# Motor_Controller_V_5.net
KiCad netlist of a schematic drawn in EAGLE
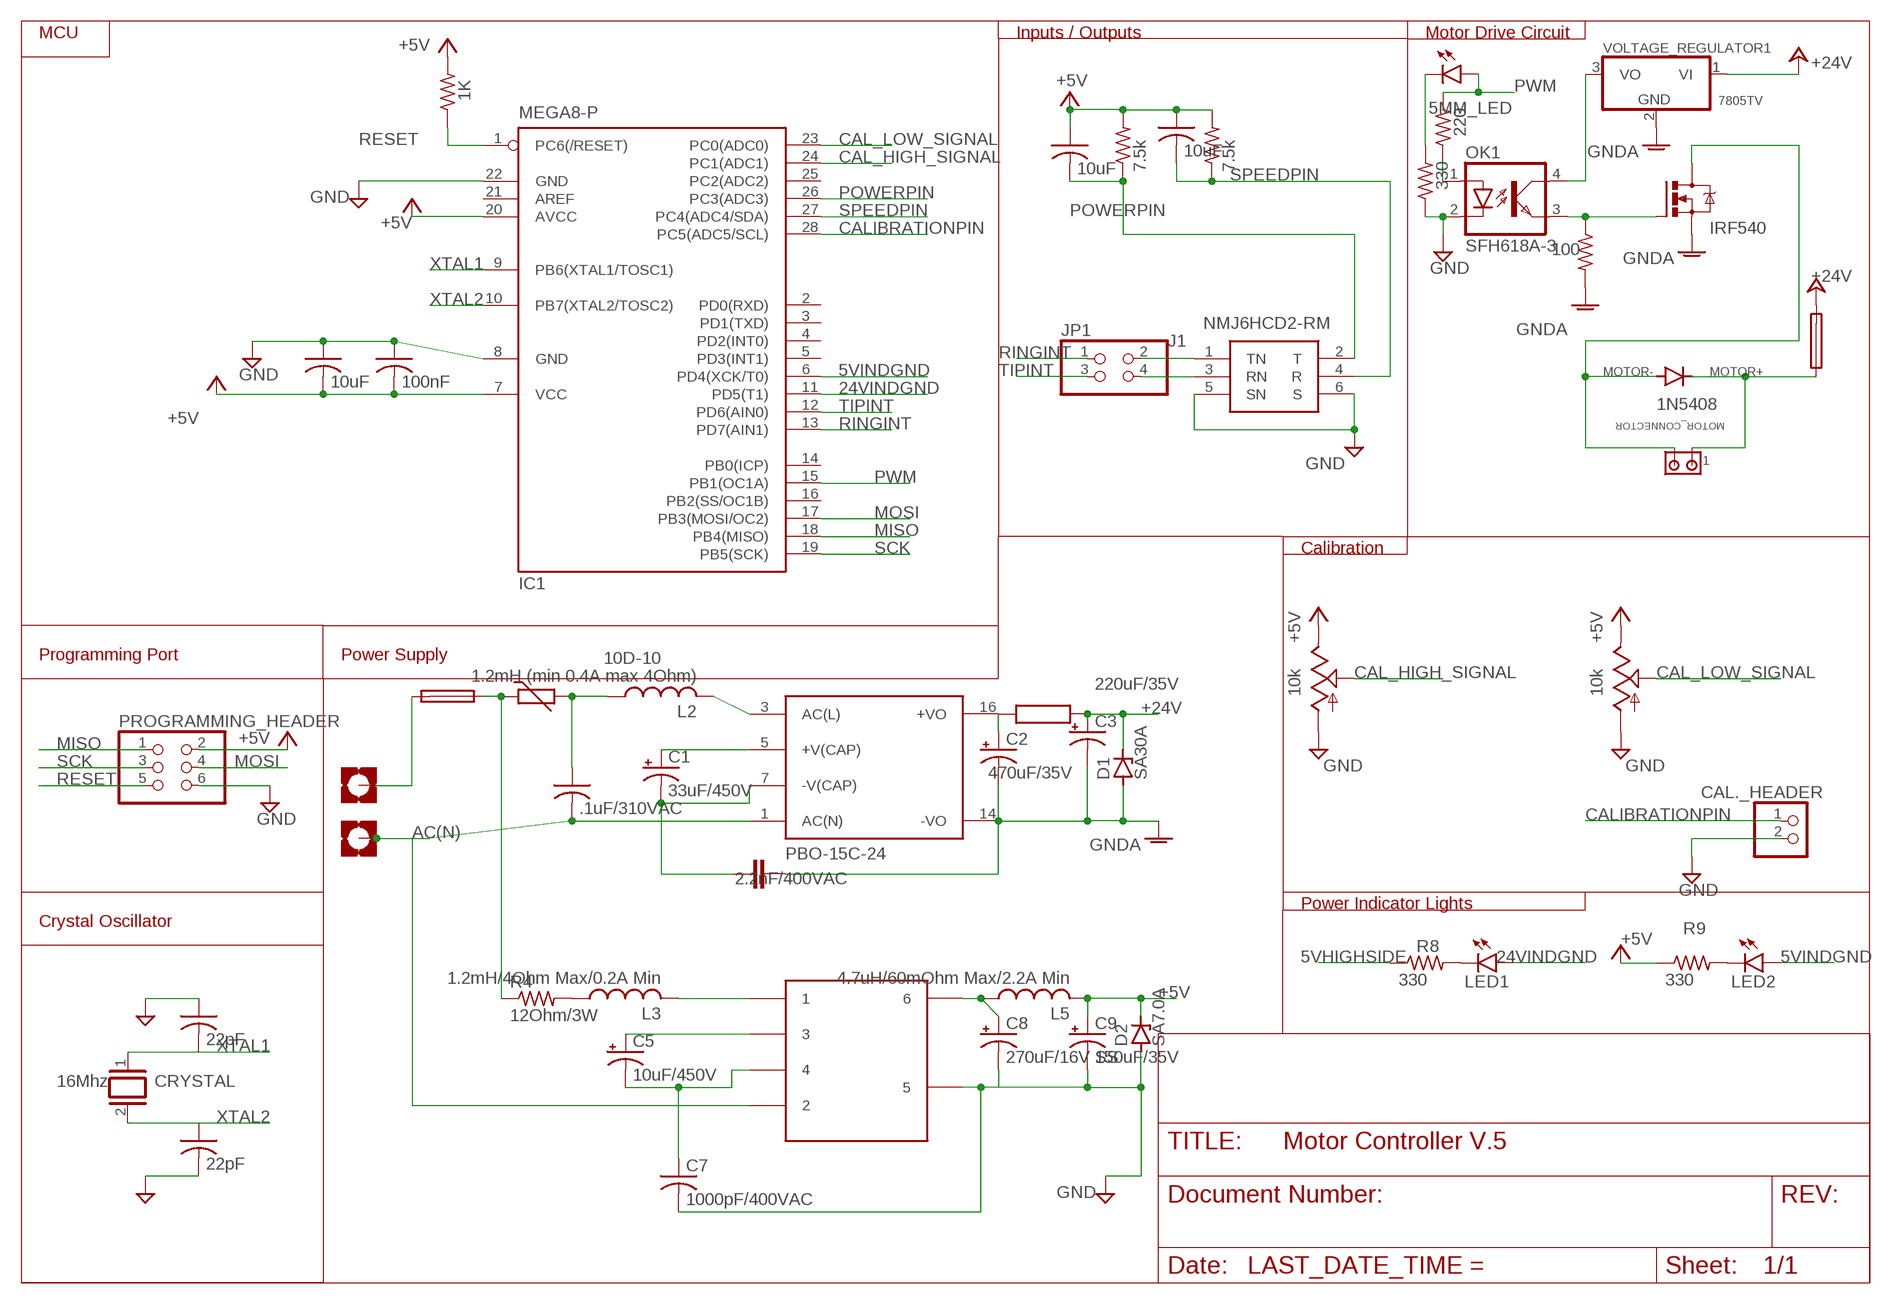
[diagram p0: schematic, sheet 1]

(export (version "E")
  (design (tool "Eeschema 10.0.6"))
  (components
    (comp (ref "1N5408")
      (value "1N5408")
      (footprint "eagle-import:DO201-15")
      (fields (field (name "MF") "VISHAY") (field (name "MPN") "1N5408-E3/54"))
      (libsource (lib "eagle-import") (part "1N5400"))
    )
    (comp (ref "AC(N)")
      (value "PAD3.0")
      (footprint "eagle-import:3,0-PAD-SQUARE")
      (libsource (lib "eagle-import") (part "PAD3.0"))
    )
    (comp (ref "C1")
      (value "33uF/450V")
      (footprint "eagle-import:E5-13")
      (libsource (lib "eagle-import") (part "CPOL-USE5-13"))
    )
    (comp (ref "C2")
      (value "470uF/35V")
      (footprint "eagle-import:E5-10,5")
      (fields (field (name "MF") "PANASONIC") (field (name "MPN") "ECA1VHG471B"))
      (libsource (lib "eagle-import") (part "CPOL-USE5-10.5"))
    )
    (comp (ref "C3")
      (value "220uF/35V")
      (footprint "eagle-import:E5-10,5")
      (fields (field (name "MF") "KEMET") (field (name "MPN") "A768KS227M1VLAE024"))
      (libsource (lib "eagle-import") (part "CPOL-USE5-10.5"))
    )
    (comp (ref "C4")
      (value ".1uF/310VAC")
      (footprint "eagle-import:C102-064X133")
      (libsource (lib "eagle-import") (part "CMPP_AC275V104K10S6"))
    )
    (comp (ref "C5")
      (value "10uF/450V")
      (footprint "eagle-import:E5-10,5")
      (libsource (lib "eagle-import") (part "CPOL-USE5-10.5"))
    )
    (comp (ref "C6")
      (value "22pF")
      (footprint "eagle-import:C025-024X044")
      (libsource (lib "eagle-import") (part "C-US025-024X044"))
    )
    (comp (ref "C7")
      (value "1000pF/400VAC")
      (footprint "eagle-import:C075-052X106")
      (libsource (lib "eagle-import") (part "C-US075-052X106"))
    )
    (comp (ref "C8")
      (value "270uF/16V SS")
      (footprint "eagle-import:E2,5-6")
      (libsource (lib "eagle-import") (part "CPOL-USE2.5-6"))
    )
    (comp (ref "C9")
      (value "150uF/35V")
      (footprint "eagle-import:E3,5-8")
      (libsource (lib "eagle-import") (part "CPOL-USE3.5-8"))
    )
    (comp (ref "C10")
      (value "10uF")
      (footprint "eagle-import:C025-024X044")
      (libsource (lib "eagle-import") (part "C-US025-024X044"))
    )
    (comp (ref "C12")
      (value "10uF")
      (footprint "eagle-import:C025-024X044")
      (libsource (lib "eagle-import") (part "C-US025-024X044"))
    )
    (comp (ref "C13")
      (value "10uF")
      (footprint "eagle-import:C025-024X044")
      (libsource (lib "eagle-import") (part "C-US025-024X044"))
    )
    (comp (ref "C14")
      (value "100nF")
      (footprint "eagle-import:C025-024X044")
      (libsource (lib "eagle-import") (part "C-US025-024X044"))
    )
    (comp (ref "C15")
      (value "22pF")
      (footprint "eagle-import:C025-024X044")
      (libsource (lib "eagle-import") (part "C-US025-024X044"))
    )
    (comp (ref "CAL._HEADER")
      (value "PINHD-1X2")
      (footprint "eagle-import:1X02")
      (libsource (lib "eagle-import") (part "PINHD-1X2"))
    )
    (comp (ref "CRYSTAL")
      (value "16Mhz")
      (footprint "eagle-import:QS")
      (libsource (lib "eagle-import") (part "XTAL/S"))
    )
    (comp (ref "CY1")
      (value "2.2nF/400VAC")
      (footprint "eagle-import:YC10B4")
      (libsource (lib "eagle-import") (part "CYYC10B4"))
    )
    (comp (ref "D1")
      (value "SA30A")
      (footprint "eagle-import:TVS-10")
      (libsource (lib "eagle-import") (part "TVSDIO"))
    )
    (comp (ref "D2")
      (value "SA7.0A")
      (footprint "eagle-import:TVS-10")
      (libsource (lib "eagle-import") (part "TVSDIO"))
    )
    (comp (ref "F1")
      (value "FUSESH22,5")
      (footprint "eagle-import:SH22,5")
      (libsource (lib "eagle-import") (part "FUSESH22,5"))
    )
    (comp (ref "F2")
      (value "1A/300V")
      (footprint "eagle-import:SH22,5")
      (libsource (lib "eagle-import") (part "FUSESH22,5"))
    )
    (comp (ref "FAST")
      (value "10k")
      (footprint "eagle-import:CT6")
      (libsource (lib "eagle-import") (part "TRIM_US-CT6"))
    )
    (comp (ref "H1")
      (value "PAD3.0")
      (footprint "eagle-import:3,0-PAD-SQUARE")
      (libsource (lib "eagle-import") (part "PAD3.0"))
    )
    (comp (ref "IC1")
      (value "MEGA8-P")
      (footprint "eagle-import:DIL28-3")
      (libsource (lib "eagle-import") (part "MEGA8-P"))
    )
    (comp (ref "J1")
      (value "NMJ6HCD2-RM")
      (footprint "eagle-import:NMJ6HCD2RM")
      (fields (field (name "MOUSER_PART_NUMBER") "568-NMJ6HCD2-RM"))
      (libsource (lib "eagle-import") (part "NMJ6HCD2-RM"))
    )
    (comp (ref "JP1")
      (value "PINHD-2X2")
      (footprint "eagle-import:2X02")
      (libsource (lib "eagle-import") (part "PINHD-2X2"))
    )
    (comp (ref "L2")
      (value "1.2mH (min 0.4A max 4Ohm)")
      (footprint "eagle-import:RCP1317_INDUCTOR")
      (libsource (lib "eagle-import") (part "RCP_1317_INDUCTOR"))
    )
    (comp (ref "L3")
      (value "1.2mH/4Ohm Max/0.2A Min")
      (footprint "eagle-import:RCP1317_INDUCTOR")
      (libsource (lib "eagle-import") (part "RCP_1317_INDUCTOR"))
    )
    (comp (ref "L5")
      (value "4.7uH/60mOhm Max/2.2A Min")
      (footprint "eagle-import:RLB0914_INDUCTOR")
      (libsource (lib "eagle-import") (part "RLB0914_INDUCTOR"))
    )
    (comp (ref "LED1")
      (value "LED3MM")
      (footprint "eagle-import:LED3MM")
      (libsource (lib "eagle-import") (part "LED3MM"))
    )
    (comp (ref "LED2")
      (value "LED3MM")
      (footprint "eagle-import:LED3MM")
      (libsource (lib "eagle-import") (part "LED3MM"))
    )
    (comp (ref "MOTOR_CONNECTOR")
      (value "MATE-N-LOK_193839-1")
      (footprint "eagle-import:MATE-N-LOK_2PIN_CONNECTOR")
      (libsource (lib "eagle-import") (part "MATE-N-LOK_193839-1"))
    )
    (comp (ref "OK1")
      (value "SFH618A-3")
      (footprint "eagle-import:DIP4")
      (fields (field (name "MF") "VISHAY/TELEFUNKEN"))
      (libsource (lib "eagle-import") (part "SFH618?A-3"))
    )
    (comp (ref "PROGRAMMING_HEADER")
      (value "PINHD-2X3")
      (footprint "eagle-import:2X03")
      (libsource (lib "eagle-import") (part "PINHD-2X3"))
    )
    (comp (ref "PS1")
      (value "PBO-15C-24")
      (footprint "eagle-import:CONV_PBO-15C-24")
      (fields (field (name "MF") "CUI Inc."))
      (libsource (lib "eagle-import") (part "PBO-15C-24"))
    )
    (comp (ref "Q1")
      (value "IRF540")
      (footprint "eagle-import:TO220BV")
      (libsource (lib "eagle-import") (part "IRF540"))
    )
    (comp (ref "R1")
      (value "10D-10")
      (footprint "eagle-import:R-7,5")
      (libsource (lib "eagle-import") (part "THERMISTOR-7,5"))
    )
    (comp (ref "R2")
      (value "1K")
      (footprint "eagle-import:0204_7")
      (libsource (lib "eagle-import") (part "R-US_0204/7"))
    )
    (comp (ref "R3")
      (value "7.5k")
      (footprint "eagle-import:0204_7")
      (libsource (lib "eagle-import") (part "R-US_0204/7"))
    )
    (comp (ref "R4")
      (value "12Ohm/3W")
      (footprint "eagle-import:VTA52")
      (libsource (lib "eagle-import") (part "R-US_VTA52"))
    )
    (comp (ref "R5")
      (value "220")
      (footprint "eagle-import:0204_7")
      (libsource (lib "eagle-import") (part "R-US_0204/7"))
    )
    (comp (ref "R6")
      (value "100")
      (footprint "eagle-import:0204_7")
      (libsource (lib "eagle-import") (part "R-US_0204/7"))
    )
    (comp (ref "R7")
      (value "7.5k")
      (footprint "eagle-import:0204_7")
      (libsource (lib "eagle-import") (part "R-US_0204/7"))
    )
    (comp (ref "R8")
      (value "330")
      (footprint "eagle-import:0204_7")
      (libsource (lib "eagle-import") (part "R-US_0204/7"))
    )
    (comp (ref "R9")
      (value "330")
      (footprint "eagle-import:0204_7")
      (libsource (lib "eagle-import") (part "R-US_0204/7"))
    )
    (comp (ref "R10")
      (value "330")
      (footprint "eagle-import:0204_7")
      (libsource (lib "eagle-import") (part "R-US_0204/7"))
    )
    (comp (ref "SLOW")
      (value "10k")
      (footprint "eagle-import:CT6")
      (libsource (lib "eagle-import") (part "TRIM_US-CT6"))
    )
    (comp (ref "U$1")
      (value "L503-13B05R")
      (footprint "eagle-import:LS03-13BO5R3")
      (libsource (lib "eagle-import") (part "L503-13B05R"))
    )
    (comp (ref "U$2")
      (value "HCTI-22-16.4")
      (footprint "eagle-import:HCTI-22-16.4")
      (libsource (lib "eagle-import") (part "HCTI-22-16.4"))
    )
    (comp (ref "U$3")
      (value "5MM_LED")
      (footprint "eagle-import:5MM_LED")
      (libsource (lib "eagle-import") (part "5MM_LED"))
    )
    (comp (ref "VOLTAGE_REGULATOR1")
      (value "7805TV")
      (footprint "eagle-import:TO220V")
      (libsource (lib "eagle-import") (part "78TV05"))
    )
  )
  (nets
    (net (code "1") (name "+5V") (class "Default")
      (node (ref "C10") (pin "1") (pinfunction "1_1") (pintype "passive"))
      (node (ref "C12") (pin "1") (pinfunction "1_1") (pintype "passive"))
      (node (ref "C13") (pin "2") (pinfunction "2_2") (pintype "passive"))
      (node (ref "C14") (pin "2") (pinfunction "2_2") (pintype "passive"))
      (node (ref "C9") (pin "+") (pinfunction "+_+") (pintype "passive"))
      (node (ref "D2") (pin "C") (pinfunction "C_C") (pintype "passive"))
      (node (ref "FAST") (pin "E") (pinfunction "E_E") (pintype "passive"))
      (node (ref "IC1") (pin "20") (pinfunction "AVCC_20") (pintype "power_in"))
      (node (ref "IC1") (pin "7") (pinfunction "VCC_7") (pintype "power_in"))
      (node (ref "L5") (pin "P$2") (pinfunction "2_P$2") (pintype "passive"))
      (node (ref "PROGRAMMING_HEADER") (pin "2") (pinfunction "2_2") (pintype "passive"))
      (node (ref "R2") (pin "2") (pinfunction "2_2") (pintype "passive"))
      (node (ref "R3") (pin "2") (pinfunction "2_2") (pintype "passive"))
      (node (ref "R7") (pin "2") (pinfunction "2_2") (pintype "passive"))
      (node (ref "R9") (pin "1") (pinfunction "1_1") (pintype "passive"))
      (node (ref "SLOW") (pin "E") (pinfunction "E_E") (pintype "passive"))
    )
    (net (code "2") (name "+24V") (class "Default")
      (node (ref "C3") (pin "+") (pinfunction "+_+") (pintype "passive"))
      (node (ref "D1") (pin "C") (pinfunction "C_C") (pintype "passive"))
      (node (ref "F1") (pin "2") (pinfunction "2_2") (pintype "passive"))
      (node (ref "U$2") (pin "P$2") (pinfunction "P$2_P$2") (pintype "bidirectional"))
      (node (ref "VOLTAGE_REGULATOR1") (pin "1") (pinfunction "VI_1") (pintype "input"))
    )
    (net (code "3") (name "/5VHIGHSIDE") (class "Default")
      (node (ref "R8") (pin "1") (pinfunction "1_1") (pintype "passive"))
    )
    (net (code "4") (name "/5VINDGND") (class "Default")
      (node (ref "IC1") (pin "6") (pinfunction "PD4(XCK/T0)_6") (pintype "bidirectional"))
      (node (ref "LED2") (pin "A") (pinfunction "A_A") (pintype "passive"))
    )
    (net (code "5") (name "/24VINDGND") (class "Default")
      (node (ref "IC1") (pin "11") (pinfunction "PD5(T1)_11") (pintype "bidirectional"))
      (node (ref "LED1") (pin "A") (pinfunction "A_A") (pintype "passive"))
    )
    (net (code "6") (name "/AC(N)") (class "Default")
      (node (ref "AC(N)") (pin "B3,0") (pinfunction "MOUNT_B3,0") (pintype "passive"))
      (node (ref "C4") (pin "2") (pinfunction "2_2") (pintype "passive"))
      (node (ref "PS1") (pin "1") (pinfunction "AC(N)_1") (pintype "input"))
      (node (ref "U$1") (pin "3") (pinfunction "2_3") (pintype "bidirectional"))
      (node (ref "U$1") (pin "4") (pinfunction "2_4") (pintype "bidirectional"))
    )
    (net (code "7") (name "/CALIBRATIONPIN") (class "Default")
      (node (ref "CAL._HEADER") (pin "1") (pinfunction "1_1") (pintype "passive"))
      (node (ref "IC1") (pin "28") (pinfunction "PC5(ADC5/SCL)_28") (pintype "bidirectional"))
    )
    (net (code "8") (name "/CAL_HIGH_SIGNAL") (class "Default")
      (node (ref "FAST") (pin "S") (pinfunction "S_S") (pintype "passive"))
      (node (ref "IC1") (pin "24") (pinfunction "PC1(ADC1)_24") (pintype "bidirectional"))
    )
    (net (code "9") (name "/CAL_LOW_SIGNAL") (class "Default")
      (node (ref "IC1") (pin "23") (pinfunction "PC0(ADC0)_23") (pintype "bidirectional"))
      (node (ref "SLOW") (pin "S") (pinfunction "S_S") (pintype "passive"))
    )
    (net (code "10") (name "/MISO") (class "Default")
      (node (ref "IC1") (pin "18") (pinfunction "PB4(MISO)_18") (pintype "bidirectional"))
      (node (ref "PROGRAMMING_HEADER") (pin "1") (pinfunction "1_1") (pintype "passive"))
    )
    (net (code "11") (name "/MOSI") (class "Default")
      (node (ref "IC1") (pin "17") (pinfunction "PB3(MOSI/OC2)_17") (pintype "bidirectional"))
      (node (ref "PROGRAMMING_HEADER") (pin "4") (pinfunction "4_4") (pintype "passive"))
    )
    (net (code "12") (name "/MOTOR+") (class "Default")
      (node (ref "1N5408") (pin "C") (pinfunction "C_C") (pintype "passive"))
      (node (ref "F1") (pin "1") (pinfunction "1_1") (pintype "passive"))
      (node (ref "MOTOR_CONNECTOR") (pin "P$1") (pinfunction "1_P$1") (pintype "passive"))
    )
    (net (code "13") (name "/MOTOR-") (class "Default")
      (node (ref "1N5408") (pin "A") (pinfunction "A_A") (pintype "passive"))
      (node (ref "MOTOR_CONNECTOR") (pin "P$2") (pinfunction "2_P$2") (pintype "passive"))
      (node (ref "Q1") (pin "D") (pinfunction "D_D") (pintype "passive"))
    )
    (net (code "14") (name "/POWERPIN") (class "Default")
      (node (ref "C10") (pin "2") (pinfunction "2_2") (pintype "passive"))
      (node (ref "IC1") (pin "26") (pinfunction "PC3(ADC3)_26") (pintype "bidirectional"))
      (node (ref "J1") (pin "2") (pinfunction "T_2") (pintype "bidirectional"))
      (node (ref "R3") (pin "1") (pinfunction "1_1") (pintype "passive"))
    )
    (net (code "15") (name "/PWM") (class "Default")
      (node (ref "IC1") (pin "15") (pinfunction "PB1(OC1A)_15") (pintype "bidirectional"))
      (node (ref "R5") (pin "2") (pinfunction "2_2") (pintype "passive"))
      (node (ref "U$3") (pin "A") (pinfunction "A_A") (pintype "passive"))
    )
    (net (code "16") (name "/RESET") (class "Default")
      (node (ref "IC1") (pin "1") (pinfunction "PC6(/RESET)_1") (pintype "bidirectional"))
      (node (ref "PROGRAMMING_HEADER") (pin "5") (pinfunction "5_5") (pintype "passive"))
      (node (ref "R2") (pin "1") (pinfunction "1_1") (pintype "passive"))
    )
    (net (code "17") (name "/RINGINT") (class "Default")
      (node (ref "IC1") (pin "13") (pinfunction "PD7(AIN1)_13") (pintype "bidirectional"))
      (node (ref "JP1") (pin "1") (pinfunction "1_1") (pintype "passive"))
    )
    (net (code "18") (name "/SCK") (class "Default")
      (node (ref "IC1") (pin "19") (pinfunction "PB5(SCK)_19") (pintype "bidirectional"))
      (node (ref "PROGRAMMING_HEADER") (pin "3") (pinfunction "3_3") (pintype "passive"))
    )
    (net (code "19") (name "/SPEEDPIN") (class "Default")
      (node (ref "C12") (pin "2") (pinfunction "2_2") (pintype "passive"))
      (node (ref "IC1") (pin "27") (pinfunction "PC4(ADC4/SDA)_27") (pintype "bidirectional"))
      (node (ref "J1") (pin "4") (pinfunction "R_4") (pintype "bidirectional"))
      (node (ref "R7") (pin "1") (pinfunction "1_1") (pintype "passive"))
    )
    (net (code "20") (name "/TIPINT") (class "Default")
      (node (ref "IC1") (pin "12") (pinfunction "PD6(AIN0)_12") (pintype "bidirectional"))
      (node (ref "JP1") (pin "3") (pinfunction "3_3") (pintype "passive"))
    )
    (net (code "21") (name "/XTAL1") (class "Default")
      (node (ref "C15") (pin "2") (pinfunction "2_2") (pintype "passive"))
      (node (ref "CRYSTAL") (pin "1") (pinfunction "1_1") (pintype "passive"))
      (node (ref "IC1") (pin "9") (pinfunction "PB6(XTAL1/TOSC1)_9") (pintype "bidirectional"))
    )
    (net (code "22") (name "/XTAL2") (class "Default")
      (node (ref "C6") (pin "1") (pinfunction "1_1") (pintype "passive"))
      (node (ref "CRYSTAL") (pin "2") (pinfunction "2_2") (pintype "passive"))
      (node (ref "IC1") (pin "10") (pinfunction "PB7(XTAL2/TOSC2)_10") (pintype "bidirectional"))
    )
    (net (code "23") (name "GND") (class "Default")
      (node (ref "C13") (pin "1") (pinfunction "1_1") (pintype "passive"))
      (node (ref "C14") (pin "1") (pinfunction "1_1") (pintype "passive"))
      (node (ref "C15") (pin "1") (pinfunction "1_1") (pintype "passive"))
      (node (ref "C6") (pin "2") (pinfunction "2_2") (pintype "passive"))
      (node (ref "C7") (pin "2") (pinfunction "2_2") (pintype "passive"))
      (node (ref "C8") (pin "-") (pinfunction "-_-") (pintype "passive"))
      (node (ref "C9") (pin "-") (pinfunction "-_-") (pintype "passive"))
      (node (ref "CAL._HEADER") (pin "2") (pinfunction "2_2") (pintype "passive"))
      (node (ref "D2") (pin "A") (pinfunction "A_A") (pintype "passive"))
      (node (ref "FAST") (pin "A") (pinfunction "A_A") (pintype "passive"))
      (node (ref "IC1") (pin "22") (pinfunction "GND_22") (pintype "power_in"))
      (node (ref "IC1") (pin "8") (pinfunction "GND_8") (pintype "power_in"))
      (node (ref "J1") (pin "5") (pinfunction "SN_5") (pintype "bidirectional"))
      (node (ref "J1") (pin "6") (pinfunction "S_6") (pintype "bidirectional"))
      (node (ref "OK1") (pin "2") (pinfunction "C_2") (pintype "passive"))
      (node (ref "PROGRAMMING_HEADER") (pin "6") (pinfunction "6_6") (pintype "passive"))
      (node (ref "R10") (pin "1") (pinfunction "1_1") (pintype "passive"))
      (node (ref "SLOW") (pin "A") (pinfunction "A_A") (pintype "passive"))
      (node (ref "U$1") (pin "10") (pinfunction "5_10") (pintype "bidirectional"))
      (node (ref "U$1") (pin "9") (pinfunction "5_9") (pintype "bidirectional"))
    )
    (net (code "24") (name "GNDA") (class "Default")
      (node (ref "C2") (pin "-") (pinfunction "-_-") (pintype "passive"))
      (node (ref "C3") (pin "-") (pinfunction "-_-") (pintype "passive"))
      (node (ref "CY1") (pin "1") (pinfunction "1_1") (pintype "passive"))
      (node (ref "D1") (pin "A") (pinfunction "A_A") (pintype "passive"))
      (node (ref "PS1") (pin "14") (pinfunction "-VO_14") (pintype "output"))
      (node (ref "Q1") (pin "S") (pinfunction "S_S") (pintype "passive"))
      (node (ref "R6") (pin "2") (pinfunction "2_2") (pintype "passive"))
      (node (ref "VOLTAGE_REGULATOR1") (pin "2") (pinfunction "GND_2") (pintype "passive"))
    )
    (net (code "25") (name "Net-(C5-Pad+)") (class "Default")
      (node (ref "C5") (pin "+") (pinfunction "+_+") (pintype "passive"))
      (node (ref "U$1") (pin "5") (pinfunction "3_5") (pintype "bidirectional"))
      (node (ref "U$1") (pin "6") (pinfunction "3_6") (pintype "bidirectional"))
    )
    (net (code "26") (name "Net-(C5-Pad-)") (class "Default")
      (node (ref "C5") (pin "-") (pinfunction "-_-") (pintype "passive"))
      (node (ref "C7") (pin "1") (pinfunction "1_1") (pintype "passive"))
      (node (ref "U$1") (pin "7") (pinfunction "4_7") (pintype "bidirectional"))
      (node (ref "U$1") (pin "8") (pinfunction "4_8") (pintype "bidirectional"))
    )
    (net (code "27") (name "Net-(F2-Pad1)") (class "Default")
      (node (ref "F2") (pin "1") (pinfunction "1_1") (pintype "passive"))
      (node (ref "R1") (pin "1") (pinfunction "1_1") (pintype "passive"))
      (node (ref "R4") (pin "1") (pinfunction "1_1") (pintype "passive"))
    )
    (net (code "28") (name "Net-(H1-MOUNT)") (class "Default")
      (node (ref "F2") (pin "2") (pinfunction "2_2") (pintype "passive"))
      (node (ref "H1") (pin "B3,0") (pinfunction "MOUNT_B3,0") (pintype "passive"))
    )
    (net (code "29") (name "Net-(J1-RN)") (class "Default")
      (node (ref "J1") (pin "3") (pinfunction "RN_3") (pintype "bidirectional"))
      (node (ref "JP1") (pin "4") (pinfunction "4_4") (pintype "passive"))
    )
    (net (code "30") (name "Net-(J1-TN)") (class "Default")
      (node (ref "J1") (pin "1") (pinfunction "TN_1") (pintype "bidirectional"))
      (node (ref "JP1") (pin "2") (pinfunction "2_2") (pintype "passive"))
    )
    (net (code "31") (name "Net-(L2-1)") (class "Default")
      (node (ref "C4") (pin "1") (pinfunction "1_1") (pintype "passive"))
      (node (ref "L2") (pin "P$1") (pinfunction "1_P$1") (pintype "passive"))
      (node (ref "R1") (pin "2") (pinfunction "2_2") (pintype "passive"))
    )
    (net (code "32") (name "Net-(L2-2)") (class "Default")
      (node (ref "L2") (pin "P$2") (pinfunction "2_P$2") (pintype "passive"))
      (node (ref "PS1") (pin "3") (pinfunction "AC(L)_3") (pintype "input"))
    )
    (net (code "33") (name "Net-(L3-1)") (class "Default")
      (node (ref "L3") (pin "P$1") (pinfunction "1_P$1") (pintype "passive"))
      (node (ref "R4") (pin "2") (pinfunction "2_2") (pintype "passive"))
    )
    (net (code "34") (name "Net-(L3-2)") (class "Default")
      (node (ref "L3") (pin "P$2") (pinfunction "2_P$2") (pintype "passive"))
      (node (ref "U$1") (pin "1") (pinfunction "1_1") (pintype "bidirectional"))
      (node (ref "U$1") (pin "2") (pinfunction "1_2") (pintype "bidirectional"))
    )
    (net (code "35") (name "Net-(L5-1)") (class "Default")
      (node (ref "C8") (pin "+") (pinfunction "+_+") (pintype "passive"))
      (node (ref "L5") (pin "P$1") (pinfunction "1_P$1") (pintype "passive"))
      (node (ref "U$1") (pin "11") (pinfunction "6_11") (pintype "bidirectional"))
      (node (ref "U$1") (pin "12") (pinfunction "6_12") (pintype "bidirectional"))
    )
    (net (code "36") (name "Net-(LED1-C)") (class "Default")
      (node (ref "LED1") (pin "K") (pinfunction "C_K") (pintype "passive"))
      (node (ref "R8") (pin "2") (pinfunction "2_2") (pintype "passive"))
    )
    (net (code "37") (name "Net-(LED2-C)") (class "Default")
      (node (ref "LED2") (pin "K") (pinfunction "C_K") (pintype "passive"))
      (node (ref "R9") (pin "2") (pinfunction "2_2") (pintype "passive"))
    )
    (net (code "38") (name "Net-(OK1-A)") (class "Default")
      (node (ref "OK1") (pin "1") (pinfunction "A_1") (pintype "passive"))
      (node (ref "R5") (pin "1") (pinfunction "1_1") (pintype "passive"))
    )
    (net (code "39") (name "Net-(OK1-COL)") (class "Default")
      (node (ref "OK1") (pin "4") (pinfunction "COL_4") (pintype "passive"))
      (node (ref "VOLTAGE_REGULATOR1") (pin "3") (pinfunction "VO_3") (pintype "passive"))
    )
    (net (code "40") (name "Net-(OK1-EMIT)") (class "Default")
      (node (ref "OK1") (pin "3") (pinfunction "EMIT_3") (pintype "passive"))
      (node (ref "Q1") (pin "G") (pinfunction "G_G") (pintype "passive"))
      (node (ref "R6") (pin "1") (pinfunction "1_1") (pintype "passive"))
    )
    (net (code "41") (name "Net-(PS1-+V(CAP))") (class "Default")
      (node (ref "C1") (pin "+") (pinfunction "+_+") (pintype "passive"))
      (node (ref "PS1") (pin "5") (pinfunction "+V(CAP)_5") (pintype "passive"))
    )
    (net (code "42") (name "Net-(PS1-+VO)") (class "Default")
      (node (ref "C2") (pin "+") (pinfunction "+_+") (pintype "passive"))
      (node (ref "PS1") (pin "16") (pinfunction "+VO_16") (pintype "output"))
      (node (ref "U$2") (pin "P$1") (pinfunction "P$1_P$1") (pintype "bidirectional"))
    )
    (net (code "43") (name "Net-(PS1--V(CAP))") (class "Default")
      (node (ref "C1") (pin "-") (pinfunction "-_-") (pintype "passive"))
      (node (ref "CY1") (pin "2") (pinfunction "2_2") (pintype "passive"))
      (node (ref "PS1") (pin "7") (pinfunction "-V(CAP)_7") (pintype "passive"))
    )
    (net (code "44") (name "Net-(R10-Pad2)") (class "Default")
      (node (ref "R10") (pin "2") (pinfunction "2_2") (pintype "passive"))
      (node (ref "U$3") (pin "C") (pinfunction "C_C") (pintype "passive"))
    )
    (net (code "45") (name "unconnected-(IC1-AREF-Pad21)") (class "Default")
      (node (ref "IC1") (pin "21") (pinfunction "AREF_21") (pintype "passive"))
    )
    (net (code "46") (name "unconnected-(IC1-PB0(ICP)-Pad14)") (class "Default")
      (node (ref "IC1") (pin "14") (pinfunction "PB0(ICP)_14") (pintype "bidirectional"))
    )
    (net (code "47") (name "unconnected-(IC1-PB2(SS{slash}OC1B)-Pad16)") (class "Default")
      (node (ref "IC1") (pin "16") (pinfunction "PB2(SS/OC1B)_16") (pintype "bidirectional"))
    )
    (net (code "48") (name "unconnected-(IC1-PC2(ADC2)-Pad25)") (class "Default")
      (node (ref "IC1") (pin "25") (pinfunction "PC2(ADC2)_25") (pintype "bidirectional"))
    )
    (net (code "49") (name "unconnected-(IC1-PD0(RXD)-Pad2)") (class "Default")
      (node (ref "IC1") (pin "2") (pinfunction "PD0(RXD)_2") (pintype "bidirectional"))
    )
    (net (code "50") (name "unconnected-(IC1-PD1(TXD)-Pad3)") (class "Default")
      (node (ref "IC1") (pin "3") (pinfunction "PD1(TXD)_3") (pintype "bidirectional"))
    )
    (net (code "51") (name "unconnected-(IC1-PD2(INT0)-Pad4)") (class "Default")
      (node (ref "IC1") (pin "4") (pinfunction "PD2(INT0)_4") (pintype "bidirectional"))
    )
    (net (code "52") (name "unconnected-(IC1-PD3(INT1)-Pad5)") (class "Default")
      (node (ref "IC1") (pin "5") (pinfunction "PD3(INT1)_5") (pintype "bidirectional"))
    )
  )
)
